# CanRelay.net
KiCad netlist of a schematic drawn in EAGLE
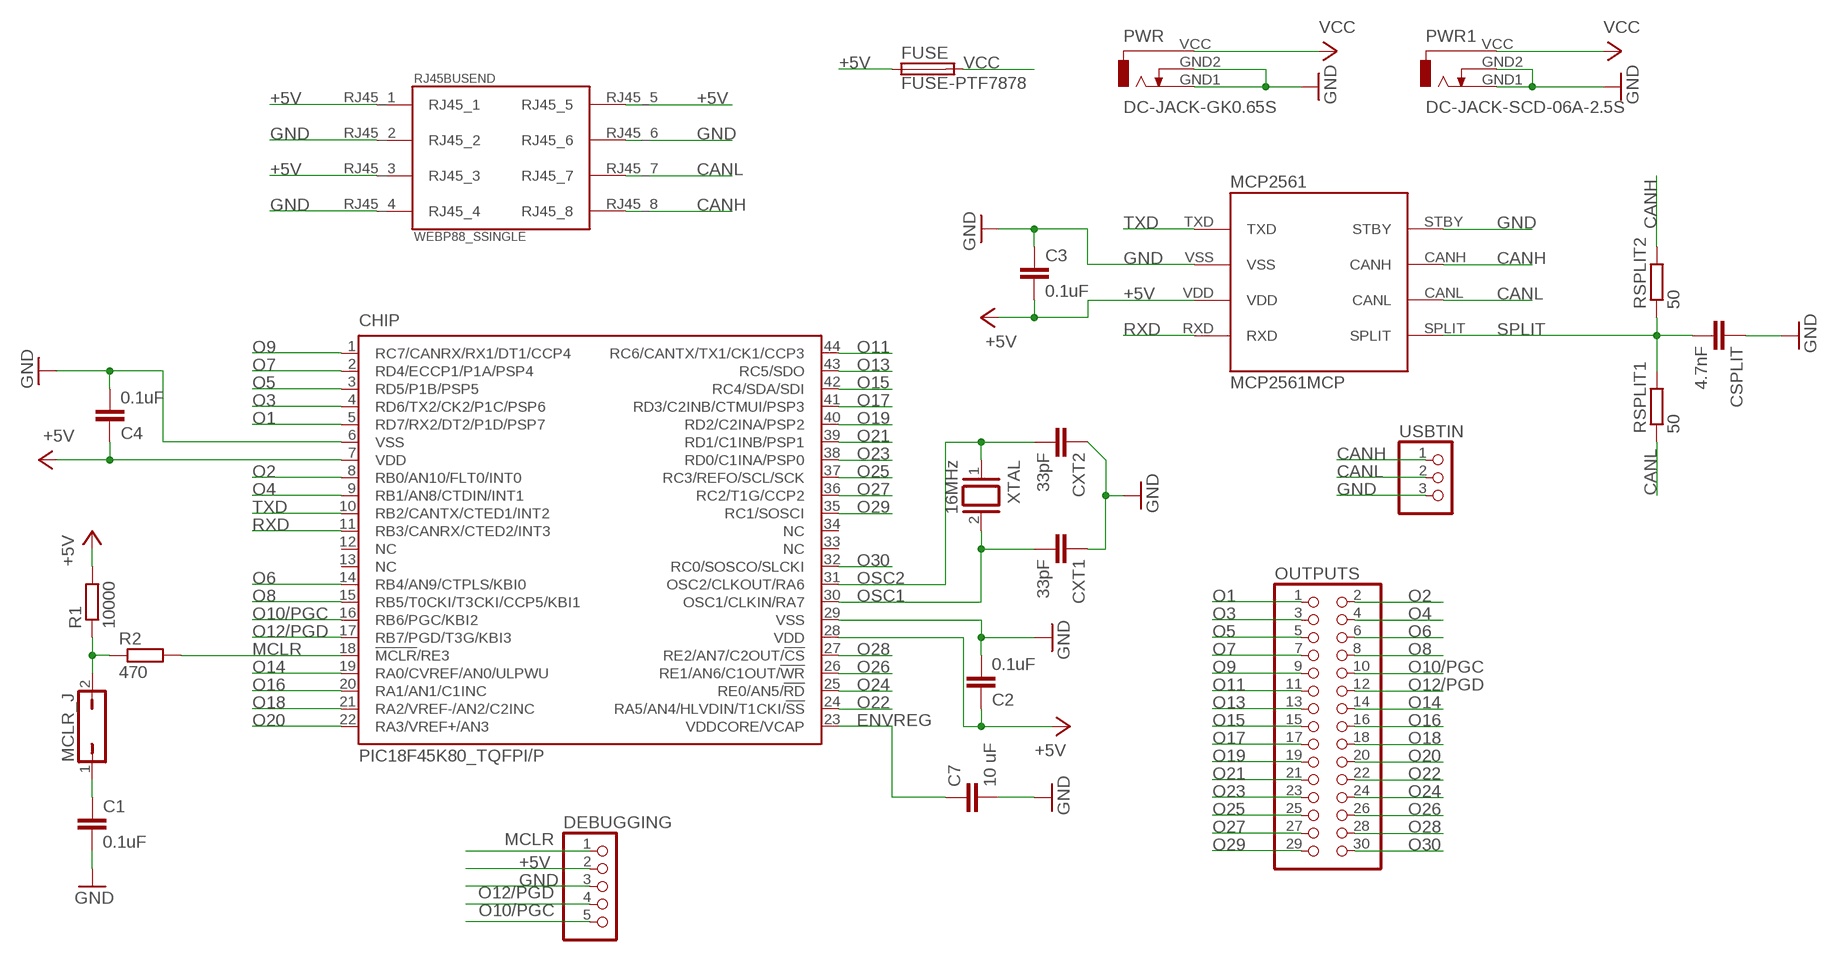
[diagram p0: schematic, sheet 1]

(export (version "E")
  (design (tool "Eeschema 10.0.6"))
  (components
    (comp (ref "C1")
      (value "0.1uF")
      (footprint "eagle-import:C050-025X075")
      (libsource (lib "eagle-import") (part "C-EU050-025X075"))
    )
    (comp (ref "C2")
      (value "0.1uF")
      (footprint "eagle-import:C050-025X075")
      (libsource (lib "eagle-import") (part "C-EU050-025X075"))
    )
    (comp (ref "C3")
      (value "0.1uF")
      (footprint "eagle-import:C050-025X075")
      (libsource (lib "eagle-import") (part "C-EU050-025X075"))
    )
    (comp (ref "C4")
      (value "0.1uF")
      (footprint "eagle-import:C050-025X075")
      (libsource (lib "eagle-import") (part "C-EU050-025X075"))
    )
    (comp (ref "C7")
      (value "10 uF")
      (footprint "eagle-import:C050-025X075")
      (libsource (lib "eagle-import") (part "C-EU050-025X075"))
    )
    (comp (ref "CHIP")
      (value "PIC18F45K80_TQFPI/P")
      (footprint "eagle-import:TQFP44")
      (libsource (lib "eagle-import") (part "PIC18F45K80_TQFPI/P"))
    )
    (comp (ref "CSPLIT")
      (value "4.7nF")
      (footprint "eagle-import:C050-025X075")
      (libsource (lib "eagle-import") (part "C-EU050-025X075"))
    )
    (comp (ref "CXT1")
      (value "33pF")
      (footprint "eagle-import:C025-030X050")
      (libsource (lib "eagle-import") (part "C-EU025-030X050"))
    )
    (comp (ref "CXT2")
      (value "33pF")
      (footprint "eagle-import:C025-030X050")
      (libsource (lib "eagle-import") (part "C-EU025-030X050"))
    )
    (comp (ref "DEBUGGING")
      (value "PINHD-1X5")
      (footprint "eagle-import:1X05")
      (libsource (lib "eagle-import") (part "PINHD-1X5"))
    )
    (comp (ref "FUSE")
      (value "FUSE-PTF7878")
      (footprint "eagle-import:FUSE-PTF78")
      (libsource (lib "eagle-import") (part "FUSE-PTF7878"))
    )
    (comp (ref "MCLR_J")
      (value "JP1Q")
      (footprint "eagle-import:JP1")
      (libsource (lib "eagle-import") (part "JP1Q"))
    )
    (comp (ref "MCP2561")
      (value "MCP2561MCP")
      (footprint "eagle-import:MCP2561_PDIP")
      (libsource (lib "eagle-import") (part "MCP2561MCP"))
    )
    (comp (ref "OUTPUTS")
      (value "PINHD-2X15")
      (footprint "eagle-import:2X15")
      (libsource (lib "eagle-import") (part "PINHD-2X15"))
    )
    (comp (ref "PWR")
      (value "DC-JACK-GK0.65S")
      (footprint "eagle-import:DC-JACK-GK0.65")
      (libsource (lib "eagle-import") (part "DC-JACK-GK0.65S"))
    )
    (comp (ref "PWR1")
      (value "DC-JACK-SCD-06A-2.5S")
      (footprint "eagle-import:DC-JACK-SCD-016A-2.5")
      (libsource (lib "eagle-import") (part "DC-JACK-SCD-06A-2.5S"))
    )
    (comp (ref "R1")
      (value "10000")
      (footprint "eagle-import:0207_10")
      (libsource (lib "eagle-import") (part "R-EU_0207/10"))
    )
    (comp (ref "R2")
      (value "470")
      (footprint "eagle-import:0207_10")
      (libsource (lib "eagle-import") (part "R-EU_0207/10"))
    )
    (comp (ref "RJ45BUSEND")
      (value "WEBP88_SSINGLE")
      (footprint "eagle-import:WEBP88_RJ45_SINGLE")
      (libsource (lib "eagle-import") (part "WEBP88_SSINGLE"))
    )
    (comp (ref "RSPLIT1")
      (value "50")
      (footprint "eagle-import:0207_10")
      (libsource (lib "eagle-import") (part "R-EU_0207/10"))
    )
    (comp (ref "RSPLIT2")
      (value "50")
      (footprint "eagle-import:0207_10")
      (libsource (lib "eagle-import") (part "R-EU_0207/10"))
    )
    (comp (ref "USBTIN")
      (value "PINHD-1X3")
      (footprint "eagle-import:1X03")
      (libsource (lib "eagle-import") (part "PINHD-1X3"))
    )
    (comp (ref "XTAL")
      (value "16MHz")
      (footprint "eagle-import:QS")
      (libsource (lib "eagle-import") (part "XTAL/S"))
    )
  )
  (nets
    (net (code "1") (name "+5V") (class "Default")
      (node (ref "C2") (pin "1") (pinfunction "1_1") (pintype "passive"))
      (node (ref "C3") (pin "2") (pinfunction "2_2") (pintype "passive"))
      (node (ref "C4") (pin "1") (pinfunction "1_1") (pintype "passive"))
      (node (ref "CHIP") (pin "28") (pinfunction "VDD_28") (pintype "power_in"))
      (node (ref "CHIP") (pin "7") (pinfunction "VDD_7") (pintype "power_in"))
      (node (ref "DEBUGGING") (pin "2") (pinfunction "2_2") (pintype "passive"))
      (node (ref "FUSE") (pin "P1") (pinfunction "1_P1") (pintype "passive"))
      (node (ref "MCP2561") (pin "VDD") (pinfunction "VDD_VDD") (pintype "bidirectional"))
      (node (ref "R1") (pin "2") (pinfunction "2_2") (pintype "passive"))
      (node (ref "RJ45BUSEND") (pin "RJ45_1") (pinfunction "RJ45_1_RJ45_1") (pintype "bidirectional"))
      (node (ref "RJ45BUSEND") (pin "RJ45_3") (pinfunction "RJ45_3_RJ45_3") (pintype "bidirectional"))
      (node (ref "RJ45BUSEND") (pin "RJ45_5") (pinfunction "RJ45_5_RJ45_5") (pintype "bidirectional"))
    )
    (net (code "2") (name "/CANH") (class "Default")
      (node (ref "MCP2561") (pin "CANH") (pinfunction "CANH_CANH") (pintype "bidirectional"))
      (node (ref "RJ45BUSEND") (pin "RJ45_8") (pinfunction "RJ45_8_RJ45_8") (pintype "bidirectional"))
      (node (ref "RSPLIT2") (pin "2") (pinfunction "2_2") (pintype "passive"))
      (node (ref "USBTIN") (pin "1") (pinfunction "1_1") (pintype "passive"))
    )
    (net (code "3") (name "/CANL") (class "Default")
      (node (ref "MCP2561") (pin "CANL") (pinfunction "CANL_CANL") (pintype "bidirectional"))
      (node (ref "RJ45BUSEND") (pin "RJ45_7") (pinfunction "RJ45_7_RJ45_7") (pintype "bidirectional"))
      (node (ref "RSPLIT1") (pin "1") (pinfunction "1_1") (pintype "passive"))
      (node (ref "USBTIN") (pin "2") (pinfunction "2_2") (pintype "passive"))
    )
    (net (code "4") (name "/ENVREG") (class "Default")
      (node (ref "C7") (pin "1") (pinfunction "1_1") (pintype "passive"))
      (node (ref "CHIP") (pin "23") (pinfunction "VDDCORE/VCAP_23") (pintype "bidirectional"))
    )
    (net (code "5") (name "/MCLR") (class "Default")
      (node (ref "CHIP") (pin "18") (pinfunction "~{MCLR}/RE3_18") (pintype "input"))
      (node (ref "DEBUGGING") (pin "1") (pinfunction "1_1") (pintype "passive"))
      (node (ref "R2") (pin "2") (pinfunction "2_2") (pintype "passive"))
    )
    (net (code "6") (name "/O1") (class "Default")
      (node (ref "CHIP") (pin "5") (pinfunction "RD7/RX2/DT2/P1D/PSP7_5") (pintype "bidirectional"))
      (node (ref "OUTPUTS") (pin "1") (pinfunction "1_1") (pintype "passive"))
    )
    (net (code "7") (name "/O2") (class "Default")
      (node (ref "CHIP") (pin "8") (pinfunction "RB0/AN10/FLT0/INT0_8") (pintype "bidirectional"))
      (node (ref "OUTPUTS") (pin "2") (pinfunction "2_2") (pintype "passive"))
    )
    (net (code "8") (name "/O3") (class "Default")
      (node (ref "CHIP") (pin "4") (pinfunction "RD6/TX2/CK2/P1C/PSP6_4") (pintype "bidirectional"))
      (node (ref "OUTPUTS") (pin "3") (pinfunction "3_3") (pintype "passive"))
    )
    (net (code "9") (name "/O4") (class "Default")
      (node (ref "CHIP") (pin "9") (pinfunction "RB1/AN8/CTDIN/INT1_9") (pintype "bidirectional"))
      (node (ref "OUTPUTS") (pin "4") (pinfunction "4_4") (pintype "passive"))
    )
    (net (code "10") (name "/O5") (class "Default")
      (node (ref "CHIP") (pin "3") (pinfunction "RD5/P1B/PSP5_3") (pintype "bidirectional"))
      (node (ref "OUTPUTS") (pin "5") (pinfunction "5_5") (pintype "passive"))
    )
    (net (code "11") (name "/O6") (class "Default")
      (node (ref "CHIP") (pin "14") (pinfunction "RB4/AN9/CTPLS/KBI0_14") (pintype "bidirectional"))
      (node (ref "OUTPUTS") (pin "6") (pinfunction "6_6") (pintype "passive"))
    )
    (net (code "12") (name "/O7") (class "Default")
      (node (ref "CHIP") (pin "2") (pinfunction "RD4/ECCP1/P1A/PSP4_2") (pintype "bidirectional"))
      (node (ref "OUTPUTS") (pin "7") (pinfunction "7_7") (pintype "passive"))
    )
    (net (code "13") (name "/O8") (class "Default")
      (node (ref "CHIP") (pin "15") (pinfunction "RB5/T0CKI/T3CKI/CCP5/KBI1_15") (pintype "bidirectional"))
      (node (ref "OUTPUTS") (pin "8") (pinfunction "8_8") (pintype "passive"))
    )
    (net (code "14") (name "/O9") (class "Default")
      (node (ref "CHIP") (pin "1") (pinfunction "RC7/CANRX/RX1/DT1/CCP4_1") (pintype "bidirectional"))
      (node (ref "OUTPUTS") (pin "9") (pinfunction "9_9") (pintype "passive"))
    )
    (net (code "15") (name "/O10{slash}PGC") (class "Default")
      (node (ref "CHIP") (pin "16") (pinfunction "RB6/PGC/KBI2_16") (pintype "bidirectional"))
      (node (ref "DEBUGGING") (pin "5") (pinfunction "5_5") (pintype "passive"))
      (node (ref "OUTPUTS") (pin "10") (pinfunction "10_10") (pintype "passive"))
    )
    (net (code "16") (name "/O11") (class "Default")
      (node (ref "CHIP") (pin "44") (pinfunction "RC6/CANTX/TX1/CK1/CCP3_44") (pintype "bidirectional"))
      (node (ref "OUTPUTS") (pin "11") (pinfunction "11_11") (pintype "passive"))
    )
    (net (code "17") (name "/O12{slash}PGD") (class "Default")
      (node (ref "CHIP") (pin "17") (pinfunction "RB7/PGD/T3G/KBI3_17") (pintype "bidirectional"))
      (node (ref "DEBUGGING") (pin "4") (pinfunction "4_4") (pintype "passive"))
      (node (ref "OUTPUTS") (pin "12") (pinfunction "12_12") (pintype "passive"))
    )
    (net (code "18") (name "/O13") (class "Default")
      (node (ref "CHIP") (pin "43") (pinfunction "RC5/SDO_43") (pintype "bidirectional"))
      (node (ref "OUTPUTS") (pin "13") (pinfunction "13_13") (pintype "passive"))
    )
    (net (code "19") (name "/O14") (class "Default")
      (node (ref "CHIP") (pin "19") (pinfunction "RA0/CVREF/AN0/ULPWU_19") (pintype "bidirectional"))
      (node (ref "OUTPUTS") (pin "14") (pinfunction "14_14") (pintype "passive"))
    )
    (net (code "20") (name "/O15") (class "Default")
      (node (ref "CHIP") (pin "42") (pinfunction "RC4/SDA/SDI_42") (pintype "bidirectional"))
      (node (ref "OUTPUTS") (pin "15") (pinfunction "15_15") (pintype "passive"))
    )
    (net (code "21") (name "/O16") (class "Default")
      (node (ref "CHIP") (pin "20") (pinfunction "RA1/AN1/C1INC_20") (pintype "bidirectional"))
      (node (ref "OUTPUTS") (pin "16") (pinfunction "16_16") (pintype "passive"))
    )
    (net (code "22") (name "/O17") (class "Default")
      (node (ref "CHIP") (pin "41") (pinfunction "RD3/C2INB/CTMUI/PSP3_41") (pintype "bidirectional"))
      (node (ref "OUTPUTS") (pin "17") (pinfunction "17_17") (pintype "passive"))
    )
    (net (code "23") (name "/O18") (class "Default")
      (node (ref "CHIP") (pin "21") (pinfunction "RA2/VREF-/AN2/C2INC_21") (pintype "bidirectional"))
      (node (ref "OUTPUTS") (pin "18") (pinfunction "18_18") (pintype "passive"))
    )
    (net (code "24") (name "/O19") (class "Default")
      (node (ref "CHIP") (pin "40") (pinfunction "RD2/C2INA/PSP2_40") (pintype "bidirectional"))
      (node (ref "OUTPUTS") (pin "19") (pinfunction "19_19") (pintype "passive"))
    )
    (net (code "25") (name "/O20") (class "Default")
      (node (ref "CHIP") (pin "22") (pinfunction "RA3/VREF+/AN3_22") (pintype "bidirectional"))
      (node (ref "OUTPUTS") (pin "20") (pinfunction "20_20") (pintype "passive"))
    )
    (net (code "26") (name "/O21") (class "Default")
      (node (ref "CHIP") (pin "39") (pinfunction "RD1/C1INB/PSP1_39") (pintype "bidirectional"))
      (node (ref "OUTPUTS") (pin "21") (pinfunction "21_21") (pintype "passive"))
    )
    (net (code "27") (name "/O22") (class "Default")
      (node (ref "CHIP") (pin "24") (pinfunction "RA5/AN4/HLVDIN/T1CKI/~{SS}_24") (pintype "bidirectional"))
      (node (ref "OUTPUTS") (pin "22") (pinfunction "22_22") (pintype "passive"))
    )
    (net (code "28") (name "/O23") (class "Default")
      (node (ref "CHIP") (pin "38") (pinfunction "RD0/C1INA/PSP0_38") (pintype "bidirectional"))
      (node (ref "OUTPUTS") (pin "23") (pinfunction "23_23") (pintype "passive"))
    )
    (net (code "29") (name "/O24") (class "Default")
      (node (ref "CHIP") (pin "25") (pinfunction "RE0/AN5/~{RD}_25") (pintype "bidirectional"))
      (node (ref "OUTPUTS") (pin "24") (pinfunction "24_24") (pintype "passive"))
    )
    (net (code "30") (name "/O25") (class "Default")
      (node (ref "CHIP") (pin "37") (pinfunction "RC3/REFO/SCL/SCK_37") (pintype "bidirectional"))
      (node (ref "OUTPUTS") (pin "25") (pinfunction "25_25") (pintype "passive"))
    )
    (net (code "31") (name "/O26") (class "Default")
      (node (ref "CHIP") (pin "26") (pinfunction "RE1/AN6/C1OUT/~{WR}_26") (pintype "bidirectional"))
      (node (ref "OUTPUTS") (pin "26") (pinfunction "26_26") (pintype "passive"))
    )
    (net (code "32") (name "/O27") (class "Default")
      (node (ref "CHIP") (pin "36") (pinfunction "RC2/T1G/CCP2_36") (pintype "bidirectional"))
      (node (ref "OUTPUTS") (pin "27") (pinfunction "27_27") (pintype "passive"))
    )
    (net (code "33") (name "/O28") (class "Default")
      (node (ref "CHIP") (pin "27") (pinfunction "RE2/AN7/C2OUT/~{CS}_27") (pintype "bidirectional"))
      (node (ref "OUTPUTS") (pin "28") (pinfunction "28_28") (pintype "passive"))
    )
    (net (code "34") (name "/O29") (class "Default")
      (node (ref "CHIP") (pin "35") (pinfunction "RC1/SOSCI_35") (pintype "bidirectional"))
      (node (ref "OUTPUTS") (pin "29") (pinfunction "29_29") (pintype "passive"))
    )
    (net (code "35") (name "/O30") (class "Default")
      (node (ref "CHIP") (pin "32") (pinfunction "RC0/SOSCO/SLCKI_32") (pintype "bidirectional"))
      (node (ref "OUTPUTS") (pin "30") (pinfunction "30_30") (pintype "passive"))
    )
    (net (code "36") (name "/OSC1") (class "Default")
      (node (ref "CHIP") (pin "30") (pinfunction "OSC1/CLKIN/RA7_30") (pintype "input"))
      (node (ref "CXT1") (pin "2") (pinfunction "2_2") (pintype "passive"))
      (node (ref "XTAL") (pin "2") (pinfunction "2_2") (pintype "passive"))
    )
    (net (code "37") (name "/OSC2") (class "Default")
      (node (ref "CHIP") (pin "31") (pinfunction "OSC2/CLKOUT/RA6_31") (pintype "output"))
      (node (ref "CXT2") (pin "2") (pinfunction "2_2") (pintype "passive"))
      (node (ref "XTAL") (pin "1") (pinfunction "1_1") (pintype "passive"))
    )
    (net (code "38") (name "/RXD") (class "Default")
      (node (ref "CHIP") (pin "11") (pinfunction "RB3/CANRX/CTED2/INT3_11") (pintype "bidirectional"))
      (node (ref "MCP2561") (pin "RXD") (pinfunction "RXD_RXD") (pintype "bidirectional"))
    )
    (net (code "39") (name "/SPLIT") (class "Default")
      (node (ref "CSPLIT") (pin "2") (pinfunction "2_2") (pintype "passive"))
      (node (ref "MCP2561") (pin "SPLIT") (pinfunction "SPLIT_SPLIT") (pintype "bidirectional"))
      (node (ref "RSPLIT1") (pin "2") (pinfunction "2_2") (pintype "passive"))
      (node (ref "RSPLIT2") (pin "1") (pinfunction "1_1") (pintype "passive"))
    )
    (net (code "40") (name "/TXD") (class "Default")
      (node (ref "CHIP") (pin "10") (pinfunction "RB2/CANTX/CTED1/INT2_10") (pintype "bidirectional"))
      (node (ref "MCP2561") (pin "TXD") (pinfunction "TXD_TXD") (pintype "bidirectional"))
    )
    (net (code "41") (name "GND") (class "Default")
      (node (ref "C1") (pin "2") (pinfunction "2_2") (pintype "passive"))
      (node (ref "C2") (pin "2") (pinfunction "2_2") (pintype "passive"))
      (node (ref "C3") (pin "1") (pinfunction "1_1") (pintype "passive"))
      (node (ref "C4") (pin "2") (pinfunction "2_2") (pintype "passive"))
      (node (ref "C7") (pin "2") (pinfunction "2_2") (pintype "passive"))
      (node (ref "CHIP") (pin "29") (pinfunction "VSS_29") (pintype "power_in"))
      (node (ref "CHIP") (pin "6") (pinfunction "VSS_6") (pintype "power_in"))
      (node (ref "CSPLIT") (pin "1") (pinfunction "1_1") (pintype "passive"))
      (node (ref "CXT1") (pin "1") (pinfunction "1_1") (pintype "passive"))
      (node (ref "CXT2") (pin "1") (pinfunction "1_1") (pintype "passive"))
      (node (ref "DEBUGGING") (pin "3") (pinfunction "3_3") (pintype "passive"))
      (node (ref "MCP2561") (pin "STBY") (pinfunction "STBY_STBY") (pintype "bidirectional"))
      (node (ref "MCP2561") (pin "VSS") (pinfunction "VSS_VSS") (pintype "bidirectional"))
      (node (ref "PWR") (pin "GND1") (pinfunction "GND1_GND1") (pintype "passive"))
      (node (ref "PWR") (pin "GND2") (pinfunction "GND2_GND2") (pintype "passive"))
      (node (ref "PWR1") (pin "GND1") (pinfunction "GND1_GND1") (pintype "passive"))
      (node (ref "PWR1") (pin "GND2") (pinfunction "GND2_GND2") (pintype "passive"))
      (node (ref "RJ45BUSEND") (pin "RJ45_2") (pinfunction "RJ45_2_RJ45_2") (pintype "bidirectional"))
      (node (ref "RJ45BUSEND") (pin "RJ45_4") (pinfunction "RJ45_4_RJ45_4") (pintype "bidirectional"))
      (node (ref "RJ45BUSEND") (pin "RJ45_6") (pinfunction "RJ45_6_RJ45_6") (pintype "bidirectional"))
      (node (ref "USBTIN") (pin "3") (pinfunction "3_3") (pintype "passive"))
    )
    (net (code "42") (name "Net-(C1-Pad1)") (class "Default")
      (node (ref "C1") (pin "1") (pinfunction "1_1") (pintype "passive"))
      (node (ref "MCLR_J") (pin "1") (pinfunction "1_1") (pintype "passive"))
    )
    (net (code "43") (name "Net-(MCLR_J-Pad2)") (class "Default")
      (node (ref "MCLR_J") (pin "2") (pinfunction "2_2") (pintype "passive"))
      (node (ref "R1") (pin "1") (pinfunction "1_1") (pintype "passive"))
      (node (ref "R2") (pin "1") (pinfunction "1_1") (pintype "passive"))
    )
    (net (code "44") (name "VCC") (class "Default")
      (node (ref "FUSE") (pin "P2") (pinfunction "2_P2") (pintype "passive"))
      (node (ref "PWR") (pin "VCC") (pinfunction "VCC_VCC") (pintype "passive"))
      (node (ref "PWR1") (pin "VCC") (pinfunction "VCC_VCC") (pintype "passive"))
    )
    (net (code "45") (name "unconnected-(CHIP-NC-Pad12)") (class "Default")
      (node (ref "CHIP") (pin "12") (pinfunction "NC_12") (pintype "bidirectional"))
    )
    (net (code "46") (name "unconnected-(CHIP-NC-Pad13)") (class "Default")
      (node (ref "CHIP") (pin "13") (pinfunction "NC_13") (pintype "bidirectional"))
    )
    (net (code "47") (name "unconnected-(CHIP-NC-Pad33)") (class "Default")
      (node (ref "CHIP") (pin "33") (pinfunction "NC_33") (pintype "input"))
    )
    (net (code "48") (name "unconnected-(CHIP-NC-Pad34)") (class "Default")
      (node (ref "CHIP") (pin "34") (pinfunction "NC_34") (pintype "input"))
    )
  )
)
